# Crowd_Guard.net
KiCad netlist of a schematic drawn in EasyEDA Pro
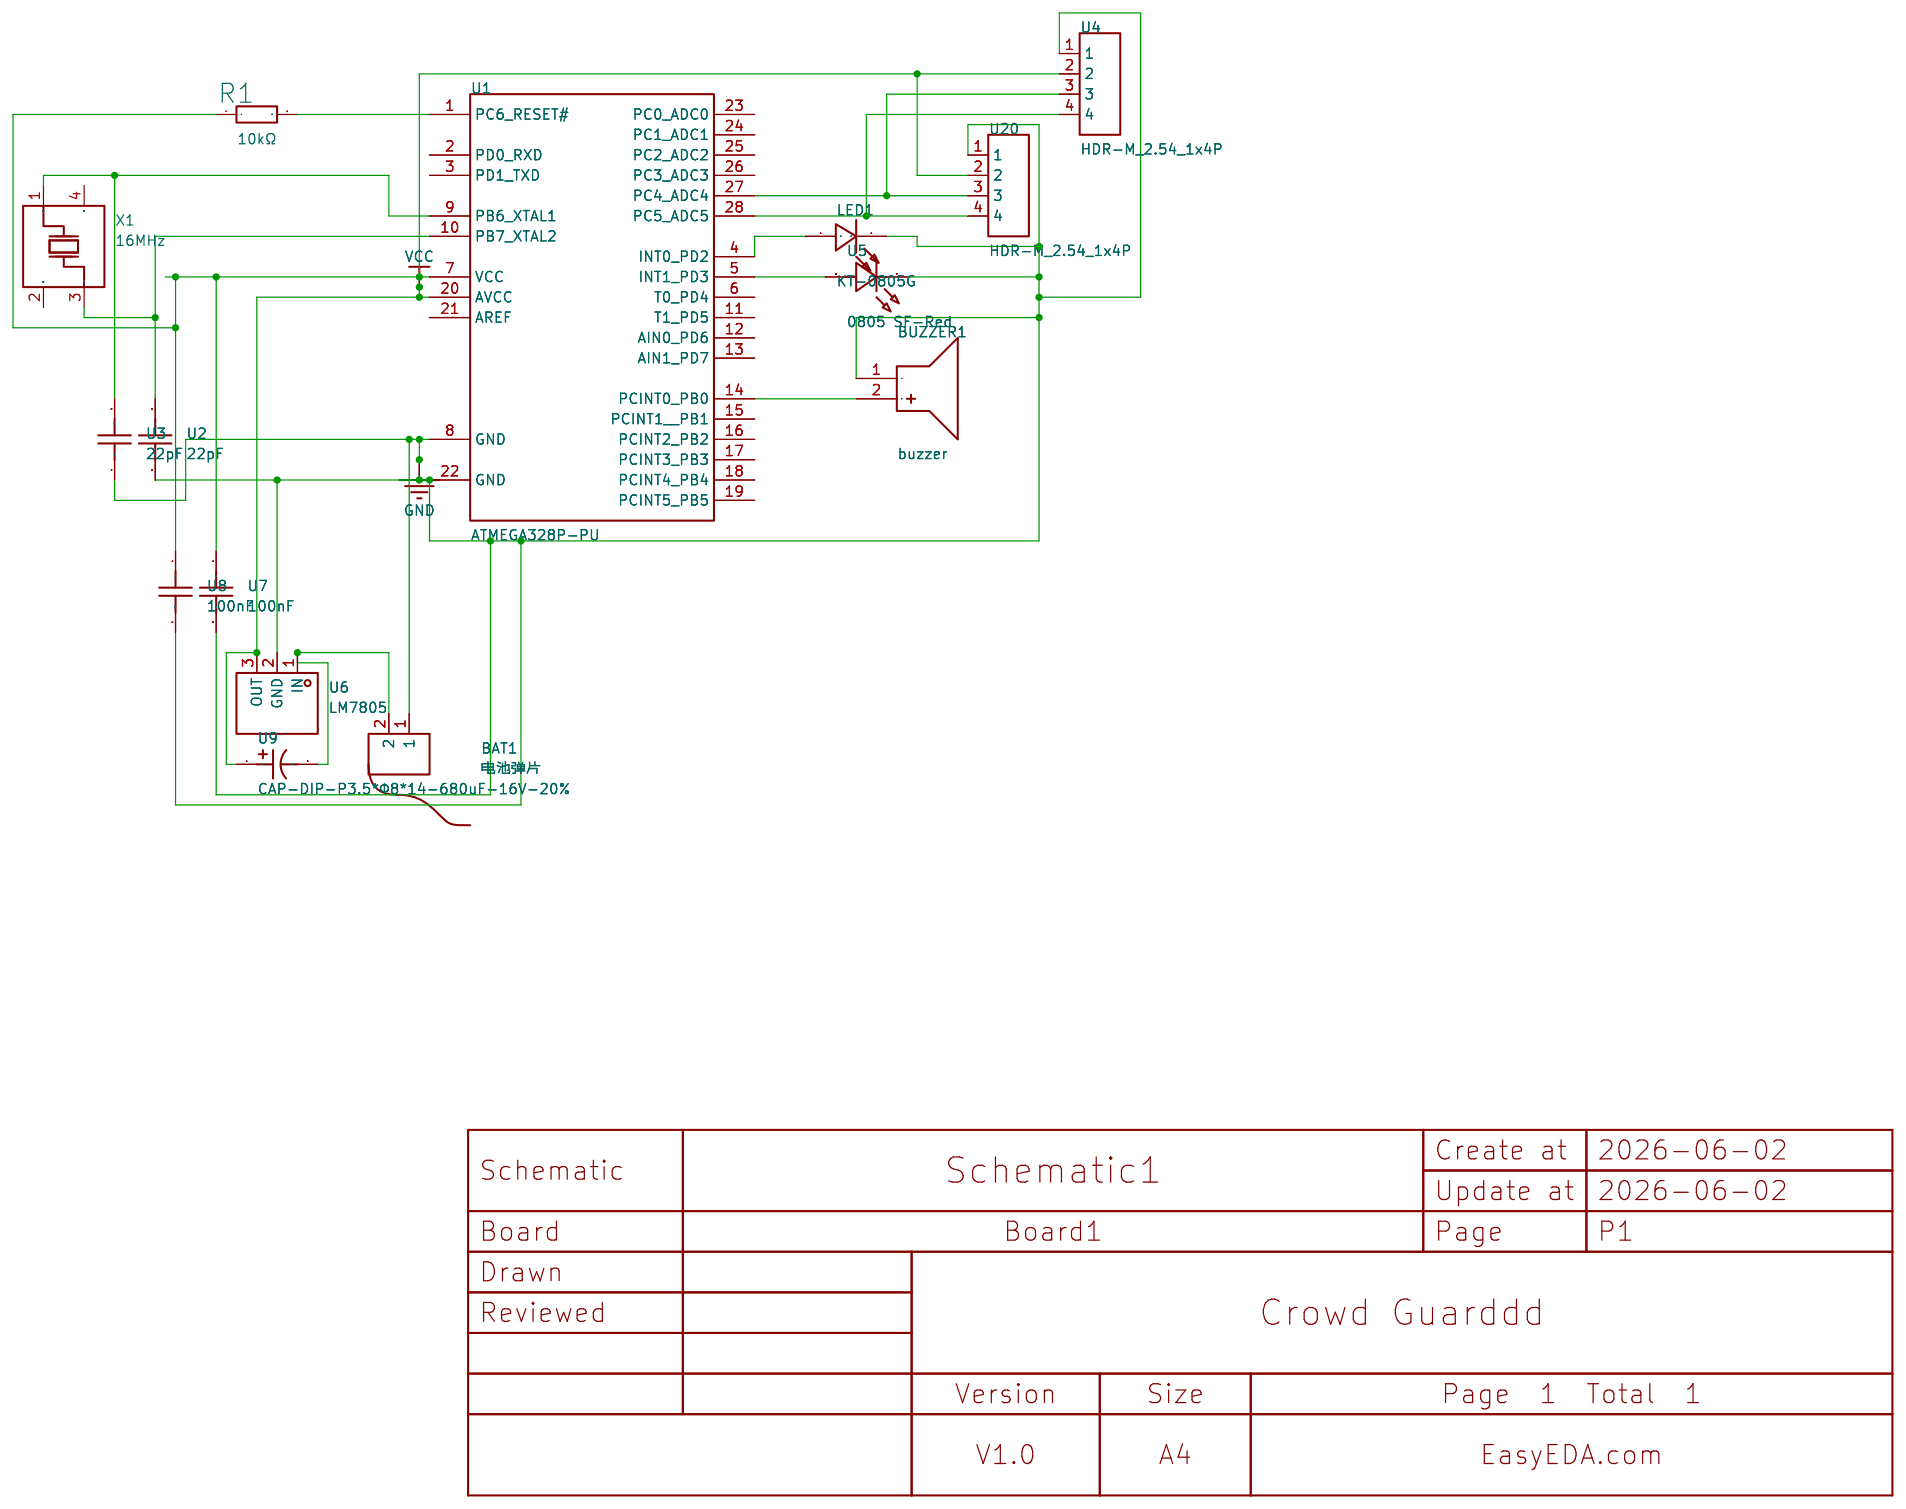
[diagram p0: schematic sheet]

(export (version "E")
  (design (tool "Eeschema 10.0.6"))
  (components
    (comp (ref "BAT1")
      (value "电池弹片")
      (footprint "easyedapro:BAT-TH_L4.0-W3.0-P3.7")
      (libsource (lib "easyedapro") (part "电池弹片_C9900020299"))
    )
    (comp (ref "BUZZER1")
      (value "buzzer")
      (footprint "easyedapro:BUZ-TH_BD12.0-P6.00-D0.9-RD")
      (libsource (lib "easyedapro") (part "BUZZER"))
    )
    (comp (ref "LED1")
      (value "KT-0805G")
      (footprint "easyedapro:LED0805-R-RD")
      (fields (field (name "Manufacturer") "KENTO"))
      (libsource (lib "easyedapro") (part "0805G (Green)"))
    )
    (comp (ref "R1")
      (value "10kΩ")
      (footprint "easyedapro:R0603")
      (fields
        (field (name "Manufacturer Part") "0603WAF1002T5E")
        (field (name "Manufacturer") "UNI-ROYAL(厚声)")
      )
      (libsource (lib "easyedapro") (part "0603WAF1002T5E"))
    )
    (comp (ref "U1")
      (value "ATMEGA328P-PU")
      (footprint "easyedapro:DIP-28_L34.6-W7.3-P2.54-LS10.2-BL")
      (fields (field (name "Manufacturer") "MICROCHIP(美国微芯)"))
      (libsource (lib "easyedapro") (part "ATMEGA328P-PU"))
    )
    (comp (ref "U2")
      (value "22pF")
      (footprint "easyedapro:C0805")
      (fields (field (name "Manufacturer Part") "C0805C220J1GACTU") (field (name "Manufacturer") "KEMET(基美)"))
      (libsource (lib "easyedapro") (part "C0805C220J1GACTU"))
    )
    (comp (ref "U3")
      (value "22pF")
      (footprint "easyedapro:C0805")
      (fields (field (name "Manufacturer Part") "C0805C220J1GACTU") (field (name "Manufacturer") "KEMET(基美)"))
      (libsource (lib "easyedapro") (part "C0805C220J1GACTU"))
    )
    (comp (ref "U4")
      (value "HDR-M_2.54_1x4P")
      (footprint "easyedapro:HDR-TH_HDR-M_2.54_1X4P")
      (libsource (lib "easyedapro") (part "HDR-M_2.54_1X4P"))
    )
    (comp (ref "U5")
      (value "0805 SF-Red")
      (footprint "easyedapro:LED0805-RD_RED")
      (libsource (lib "easyedapro") (part "0805 SF-RED"))
    )
    (comp (ref "U6")
      (value "LM7805")
      (footprint "easyedapro:TO-220-3_L10.0-W4.5-P2.54-L")
      (fields (field (name "Manufacturer") "TF(拓锋)"))
      (libsource (lib "easyedapro") (part "LM7805"))
    )
    (comp (ref "U7")
      (value "100nF")
      (footprint "easyedapro:CAP-TH_L5.0-W2.5-P5.00-D1.0")
      (libsource (lib "easyedapro") (part "100NF_C9900015256"))
    )
    (comp (ref "U8")
      (value "100nF")
      (footprint "easyedapro:CAP-TH_L5.0-W2.5-P5.00-D1.0")
      (libsource (lib "easyedapro") (part "100NF_C9900015256"))
    )
    (comp (ref "U9")
      (value "CAP-DIP-P3.5*Φ8*14-680uF-16V-20%")
      (footprint "easyedapro:CAP-TH_BD8.0-P3.50-D0.5-FD")
      (libsource (lib "easyedapro") (part "CAP-DIP-P3.5*Φ8*14-680UF-16V-20%"))
    )
    (comp (ref "U20")
      (value "HDR-M_2.54_1x4P")
      (footprint "easyedapro:HDR-TH_HDR-M_2.54_1X4P")
      (libsource (lib "easyedapro") (part "HDR-M_2.54_1X4P"))
    )
    (comp (ref "X1")
      (value "16MHz")
      (footprint "easyedapro:CRYSTAL-SMD_4P-L3.2-W2.5-BL")
      (fields (field (name "Manufacturer Part") "X322516MLB4SI") (field (name "Manufacturer") "YXC(扬兴晶振)"))
      (libsource (lib "easyedapro") (part "X322516MLB4SI"))
    )
  )
  (nets
    (net (code "1") (name "GND") (class "Default")
      (node (ref "BAT1") (pin "1") (pinfunction "1_1") (pintype "unspecified"))
      (node (ref "BUZZER1") (pin "1") (pinfunction "-_1") (pintype "unspecified"))
      (node (ref "LED1") (pin "2") (pinfunction "K_2") (pintype "unspecified"))
      (node (ref "U1") (pin "22") (pinfunction "GND_22") (pintype "unspecified"))
      (node (ref "U1") (pin "8") (pinfunction "GND_8") (pintype "unspecified"))
      (node (ref "U2") (pin "1") (pinfunction "1_1") (pintype "unspecified"))
      (node (ref "U20") (pin "1") (pinfunction "1_1") (pintype "unspecified"))
      (node (ref "U3") (pin "1") (pinfunction "1_1") (pintype "unspecified"))
      (node (ref "U4") (pin "1") (pinfunction "1_1") (pintype "unspecified"))
      (node (ref "U5") (pin "1") (pinfunction "K_1") (pintype "unspecified"))
      (node (ref "U6") (pin "2") (pinfunction "GND_2") (pintype "input"))
      (node (ref "U7") (pin "2") (pinfunction "2_2") (pintype "unspecified"))
      (node (ref "U8") (pin "2") (pinfunction "2_2") (pintype "unspecified"))
    )
    (net (code "2") (name "Net-(BUZZER1-+)") (class "Default")
      (node (ref "BUZZER1") (pin "2") (pinfunction "+_2") (pintype "unspecified"))
      (node (ref "U1") (pin "14") (pinfunction "PCINT0_PB0_14") (pintype "bidirectional"))
    )
    (net (code "3") (name "Net-(LED1-A)") (class "Default")
      (node (ref "LED1") (pin "1") (pinfunction "A_1") (pintype "unspecified"))
      (node (ref "U1") (pin "4") (pinfunction "INT0_PD2_4") (pintype "bidirectional"))
    )
    (net (code "4") (name "Net-(U1-INT1_PD3)") (class "Default")
      (node (ref "U1") (pin "5") (pinfunction "INT1_PD3_5") (pintype "bidirectional"))
      (node (ref "U5") (pin "2") (pinfunction "A_2") (pintype "unspecified"))
    )
    (net (code "5") (name "Net-(U1-PB6_XTAL1)") (class "Default")
      (node (ref "U1") (pin "9") (pinfunction "PB6_XTAL1_9") (pintype "bidirectional"))
      (node (ref "U3") (pin "2") (pinfunction "2_2") (pintype "unspecified"))
      (node (ref "X1") (pin "1") (pinfunction "OSC1_1") (pintype "unspecified"))
    )
    (net (code "6") (name "Net-(U1-PB7_XTAL2)") (class "Default")
      (node (ref "U1") (pin "10") (pinfunction "PB7_XTAL2_10") (pintype "bidirectional"))
      (node (ref "U2") (pin "2") (pinfunction "2_2") (pintype "unspecified"))
      (node (ref "X1") (pin "3") (pinfunction "OSC2_3") (pintype "unspecified"))
    )
    (net (code "7") (name "Net-(U1-PC4_ADC4)") (class "Default")
      (node (ref "U1") (pin "27") (pinfunction "PC4_ADC4_27") (pintype "bidirectional"))
      (node (ref "U20") (pin "3") (pinfunction "3_3") (pintype "unspecified"))
      (node (ref "U4") (pin "3") (pinfunction "3_3") (pintype "unspecified"))
    )
    (net (code "8") (name "Net-(U1-PC5_ADC5)") (class "Default")
      (node (ref "U1") (pin "28") (pinfunction "PC5_ADC5_28") (pintype "bidirectional"))
      (node (ref "U20") (pin "4") (pinfunction "4_4") (pintype "unspecified"))
      (node (ref "U4") (pin "4") (pinfunction "4_4") (pintype "unspecified"))
    )
    (net (code "9") (name "Net-(U1-PC6_RESET#)") (class "Default")
      (node (ref "R1") (pin "2") (pinfunction "2_2") (pintype "input"))
      (node (ref "U1") (pin "1") (pinfunction "PC6_RESET#_1") (pintype "bidirectional"))
    )
    (net (code "10") (name "Net-(U6-IN)") (class "Default")
      (node (ref "BAT1") (pin "2") (pinfunction "2_2") (pintype "unspecified"))
      (node (ref "U6") (pin "1") (pinfunction "IN_1") (pintype "input"))
      (node (ref "U9") (pin "2") (pinfunction "2_2") (pintype "input"))
    )
    (net (code "11") (name "VCC") (class "Default")
      (node (ref "R1") (pin "1") (pinfunction "1_1") (pintype "input"))
      (node (ref "U1") (pin "20") (pinfunction "AVCC_20") (pintype "unspecified"))
      (node (ref "U1") (pin "7") (pinfunction "VCC_7") (pintype "unspecified"))
      (node (ref "U20") (pin "2") (pinfunction "2_2") (pintype "unspecified"))
      (node (ref "U4") (pin "2") (pinfunction "2_2") (pintype "unspecified"))
      (node (ref "U6") (pin "3") (pinfunction "OUT_3") (pintype "input"))
      (node (ref "U7") (pin "1") (pinfunction "1_1") (pintype "unspecified"))
      (node (ref "U8") (pin "1") (pinfunction "1_1") (pintype "unspecified"))
      (node (ref "U9") (pin "1") (pinfunction "1_1") (pintype "input"))
    )
    (net (code "12") (name "unconnected-(U1-AIN0_PD6-Pad12)") (class "Default")
      (node (ref "U1") (pin "12") (pinfunction "AIN0_PD6_12") (pintype "bidirectional"))
    )
    (net (code "13") (name "unconnected-(U1-AIN1_PD7-Pad13)") (class "Default")
      (node (ref "U1") (pin "13") (pinfunction "AIN1_PD7_13") (pintype "bidirectional"))
    )
    (net (code "14") (name "unconnected-(U1-AREF-Pad21)") (class "Default")
      (node (ref "U1") (pin "21") (pinfunction "AREF_21") (pintype "unspecified"))
    )
    (net (code "15") (name "unconnected-(U1-PC0_ADC0-Pad23)") (class "Default")
      (node (ref "U1") (pin "23") (pinfunction "PC0_ADC0_23") (pintype "bidirectional"))
    )
    (net (code "16") (name "unconnected-(U1-PC1_ADC1-Pad24)") (class "Default")
      (node (ref "U1") (pin "24") (pinfunction "PC1_ADC1_24") (pintype "bidirectional"))
    )
    (net (code "17") (name "unconnected-(U1-PC2_ADC2-Pad25)") (class "Default")
      (node (ref "U1") (pin "25") (pinfunction "PC2_ADC2_25") (pintype "bidirectional"))
    )
    (net (code "18") (name "unconnected-(U1-PC3_ADC3-Pad26)") (class "Default")
      (node (ref "U1") (pin "26") (pinfunction "PC3_ADC3_26") (pintype "bidirectional"))
    )
    (net (code "19") (name "unconnected-(U1-PCINT1__PB1-Pad15)") (class "Default")
      (node (ref "U1") (pin "15") (pinfunction "PCINT1__PB1_15") (pintype "bidirectional"))
    )
    (net (code "20") (name "unconnected-(U1-PCINT2_PB2-Pad16)") (class "Default")
      (node (ref "U1") (pin "16") (pinfunction "PCINT2_PB2_16") (pintype "bidirectional"))
    )
    (net (code "21") (name "unconnected-(U1-PCINT3_PB3-Pad17)") (class "Default")
      (node (ref "U1") (pin "17") (pinfunction "PCINT3_PB3_17") (pintype "bidirectional"))
    )
    (net (code "22") (name "unconnected-(U1-PCINT4_PB4-Pad18)") (class "Default")
      (node (ref "U1") (pin "18") (pinfunction "PCINT4_PB4_18") (pintype "bidirectional"))
    )
    (net (code "23") (name "unconnected-(U1-PCINT5_PB5-Pad19)") (class "Default")
      (node (ref "U1") (pin "19") (pinfunction "PCINT5_PB5_19") (pintype "bidirectional"))
    )
    (net (code "24") (name "unconnected-(U1-PD0_RXD-Pad2)") (class "Default")
      (node (ref "U1") (pin "2") (pinfunction "PD0_RXD_2") (pintype "bidirectional"))
    )
    (net (code "25") (name "unconnected-(U1-PD1_TXD-Pad3)") (class "Default")
      (node (ref "U1") (pin "3") (pinfunction "PD1_TXD_3") (pintype "bidirectional"))
    )
    (net (code "26") (name "unconnected-(U1-T0_PD4-Pad6)") (class "Default")
      (node (ref "U1") (pin "6") (pinfunction "T0_PD4_6") (pintype "bidirectional"))
    )
    (net (code "27") (name "unconnected-(U1-T1_PD5-Pad11)") (class "Default")
      (node (ref "U1") (pin "11") (pinfunction "T1_PD5_11") (pintype "bidirectional"))
    )
    (net (code "28") (name "unconnected-(X1-GND-Pad2)") (class "Default")
      (node (ref "X1") (pin "2") (pinfunction "GND_2") (pintype "unspecified"))
    )
    (net (code "29") (name "unconnected-(X1-GND-Pad4)") (class "Default")
      (node (ref "X1") (pin "4") (pinfunction "GND_4") (pintype "unspecified"))
    )
  )
)
